# FastFoto.net
KiCad netlist of a schematic drawn in EAGLE
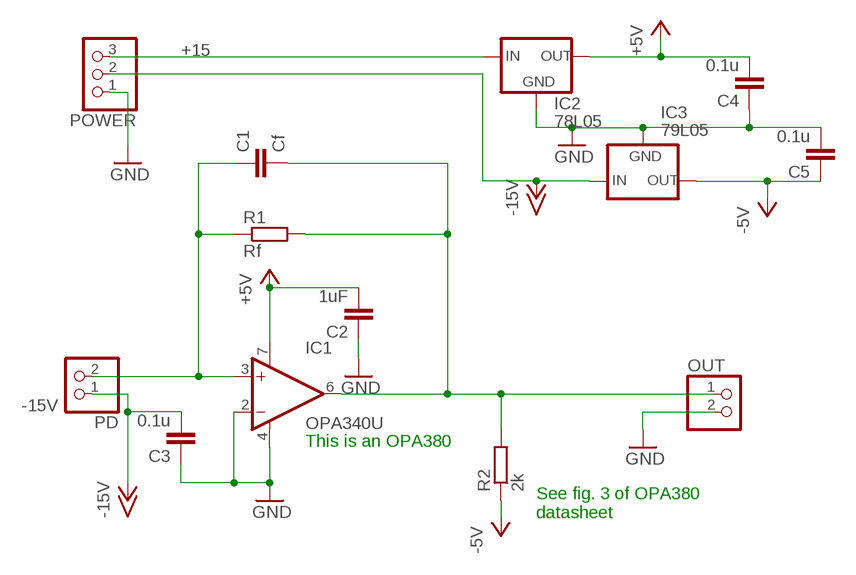
[diagram p0: schematic, sheet 1]

(export (version "E")
  (design (tool "Eeschema 10.0.6"))
  (components
    (comp (ref "C1")
      (value "Cf")
      (footprint "eagle-import:C050-030X075")
      (libsource (lib "eagle-import") (part "C-EU050-030X075"))
    )
    (comp (ref "C2")
      (value "1uF")
      (footprint "eagle-import:C050-030X075")
      (libsource (lib "eagle-import") (part "C-EU050-030X075"))
    )
    (comp (ref "C3")
      (value "0.1u")
      (footprint "eagle-import:C050-030X075")
      (libsource (lib "eagle-import") (part "C-EU050-030X075"))
    )
    (comp (ref "C4")
      (value "0.1u")
      (footprint "eagle-import:C050-030X075")
      (libsource (lib "eagle-import") (part "C-EU050-030X075"))
    )
    (comp (ref "C5")
      (value "0.1u")
      (footprint "eagle-import:C050-030X075")
      (libsource (lib "eagle-import") (part "C-EU050-030X075"))
    )
    (comp (ref "IC1")
      (value "OPA340U")
      (footprint "eagle-import:SO08")
      (fields (field (name "MPN") "OPA340UA"))
      (libsource (lib "eagle-import") (part "OPA340U"))
    )
    (comp (ref "IC2")
      (value "78L05")
      (footprint "eagle-import:78LXX")
      (libsource (lib "eagle-import") (part "78LXX"))
    )
    (comp (ref "IC3")
      (value "79L05")
      (footprint "eagle-import:79LXX")
      (libsource (lib "eagle-import") (part "79LXX"))
    )
    (comp (ref "OUT")
      (value "PINHD-1X2")
      (footprint "eagle-import:1X02")
      (libsource (lib "eagle-import") (part "PINHD-1X2"))
    )
    (comp (ref "PD")
      (value "PINHD-1X2")
      (footprint "eagle-import:1X02")
      (libsource (lib "eagle-import") (part "PINHD-1X2"))
    )
    (comp (ref "POWER")
      (value "PINHD-1X3")
      (footprint "eagle-import:1X03")
      (libsource (lib "eagle-import") (part "PINHD-1X3"))
    )
    (comp (ref "R1")
      (value "Rf")
      (footprint "eagle-import:0204_7")
      (libsource (lib "eagle-import") (part "R-EU_0204/7"))
    )
    (comp (ref "R2")
      (value "2k")
      (footprint "eagle-import:0204_7")
      (libsource (lib "eagle-import") (part "R-EU_0204/7"))
    )
  )
  (nets
    (net (code "1") (name "+5V") (class "Default")
      (node (ref "C2") (pin "2") (pinfunction "2_2") (pintype "passive"))
      (node (ref "C4") (pin "2") (pinfunction "2_2") (pintype "passive"))
      (node (ref "IC1") (pin "7") (pinfunction "V+_7") (pintype "power_in"))
      (node (ref "IC2") (pin "OUT") (pinfunction "OUT_OUT") (pintype "passive"))
    )
    (net (code "2") (name "-5V") (class "Default")
      (node (ref "C5") (pin "1") (pinfunction "1_1") (pintype "passive"))
      (node (ref "IC3") (pin "OUT") (pinfunction "OUT_OUT") (pintype "passive"))
      (node (ref "R2") (pin "1") (pinfunction "1_1") (pintype "passive"))
    )
    (net (code "3") (name "-15V") (class "Default")
      (node (ref "C3") (pin "2") (pinfunction "2_2") (pintype "passive"))
      (node (ref "IC3") (pin "IN") (pinfunction "IN_IN") (pintype "input"))
      (node (ref "PD") (pin "1") (pinfunction "1_1") (pintype "passive"))
      (node (ref "POWER") (pin "2") (pinfunction "2_2") (pintype "passive"))
    )
    (net (code "4") (name "/+15") (class "Default")
      (node (ref "IC2") (pin "IN") (pinfunction "IN_IN") (pintype "input"))
      (node (ref "POWER") (pin "3") (pinfunction "3_3") (pintype "passive"))
    )
    (net (code "5") (name "GND") (class "Default")
      (node (ref "C2") (pin "1") (pinfunction "1_1") (pintype "passive"))
      (node (ref "C3") (pin "1") (pinfunction "1_1") (pintype "passive"))
      (node (ref "C4") (pin "1") (pinfunction "1_1") (pintype "passive"))
      (node (ref "C5") (pin "2") (pinfunction "2_2") (pintype "passive"))
      (node (ref "IC1") (pin "2") (pinfunction "-IN_2") (pintype "input"))
      (node (ref "IC1") (pin "4") (pinfunction "V-_4") (pintype "power_in"))
      (node (ref "IC2") (pin "GND") (pinfunction "GND_GND") (pintype "input"))
      (node (ref "IC3") (pin "GND") (pinfunction "GND_GND") (pintype "input"))
      (node (ref "OUT") (pin "2") (pinfunction "2_2") (pintype "passive"))
      (node (ref "POWER") (pin "1") (pinfunction "1_1") (pintype "passive"))
    )
    (net (code "6") (name "Net-(IC1-+IN)") (class "Default")
      (node (ref "C1") (pin "1") (pinfunction "1_1") (pintype "passive"))
      (node (ref "IC1") (pin "3") (pinfunction "+IN_3") (pintype "input"))
      (node (ref "PD") (pin "2") (pinfunction "2_2") (pintype "passive"))
      (node (ref "R1") (pin "1") (pinfunction "1_1") (pintype "passive"))
    )
    (net (code "7") (name "Net-(IC1-OUT)") (class "Default")
      (node (ref "C1") (pin "2") (pinfunction "2_2") (pintype "passive"))
      (node (ref "IC1") (pin "6") (pinfunction "OUT_6") (pintype "output"))
      (node (ref "OUT") (pin "1") (pinfunction "1_1") (pintype "passive"))
      (node (ref "R1") (pin "2") (pinfunction "2_2") (pintype "passive"))
      (node (ref "R2") (pin "2") (pinfunction "2_2") (pintype "passive"))
    )
  )
)
